# IQModulatorWaveyRadar.net
KiCad netlist of a schematic drawn in Altium Designer
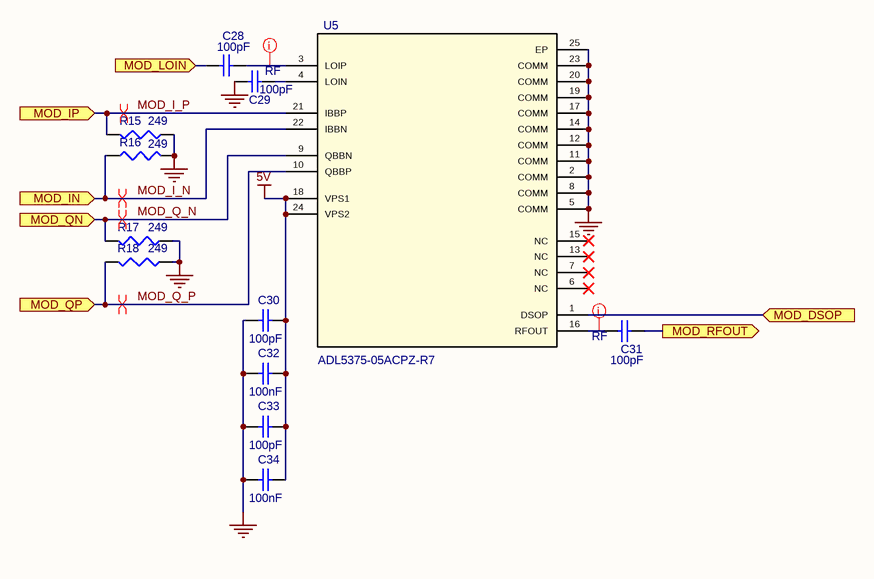
[diagram p0: IQModulatorWaveyRadar.SchDoc]

(export (version "E")
  (design (tool "Eeschema 10.0.6"))
  (components
    (comp (ref "C28")
      (value "100pF")
      (footprint "CAPC1005X56X25LL10T15")
      (fields (field (name "Comment") "04023A101JAT2A"))
      (libsource (lib "University of South Florida") (part "CAP-NP-2"))
    )
    (comp (ref "C29")
      (value "100pF")
      (footprint "CAPC1005X56X25LL10T15")
      (fields (field (name "Comment") "04023A101JAT2A"))
      (libsource (lib "University of South Florida") (part "CAP-NP-2"))
    )
    (comp (ref "C30")
      (value "100pF")
      (footprint "CAPC1005X56X25LL10T15")
      (fields (field (name "Comment") "04023A101JAT2A"))
      (libsource (lib "University of South Florida") (part "CAP-NP-2"))
    )
    (comp (ref "C31")
      (value "100pF")
      (footprint "CAPC1005X56X25LL10T15")
      (fields (field (name "Comment") "04023A101JAT2A"))
      (libsource (lib "University of South Florida") (part "CAP-NP-2"))
    )
    (comp (ref "C32")
      (value "100nF")
      (footprint "CAPC0402(1005)60_L")
      (description "Chip Capacitor, 100nF +/-20%, 10V, 0402, Thickness 0.6 mm")
      (fields (field (name "TOLERANCE") "20%") (field (name "Comment") "Capacitor 100nF +/-20% 10V 0402"))
      (libsource (lib "University of South Florida") (part "CAP-NP-2"))
    )
    (comp (ref "C33")
      (value "100pF")
      (footprint "CAPC1005X56X25LL10T15")
      (fields (field (name "Comment") "04023A101JAT2A"))
      (libsource (lib "University of South Florida") (part "CAP-NP-2"))
    )
    (comp (ref "C34")
      (value "100nF")
      (footprint "CAPC0402(1005)60_L")
      (description "Chip Capacitor, 100nF +/-20%, 10V, 0402, Thickness 0.6 mm")
      (fields (field (name "TOLERANCE") "20%") (field (name "Comment") "Capacitor 100nF +/-20% 10V 0402"))
      (libsource (lib "University of South Florida") (part "CAP-NP-2"))
    )
    (comp (ref "R15")
      (value "249")
      (footprint "RESC1005X40X25NL05T05")
      (description "RESISTOR, 0402, 249R 1%, 0.1W")
      (fields (field (name "Comment") "ERJ-2RKF2490X"))
      (libsource (lib "University of South Florida") (part "ResistorSymbol"))
    )
    (comp (ref "R16")
      (value "249")
      (footprint "RESC1005X40X25NL05T05")
      (description "RESISTOR, 0402, 249R 1%, 0.1W")
      (fields (field (name "Comment") "ERJ-2RKF2490X"))
      (libsource (lib "University of South Florida") (part "ResistorSymbol"))
    )
    (comp (ref "R17")
      (value "249")
      (footprint "RESC1005X40X25NL05T05")
      (description "RESISTOR, 0402, 249R 1%, 0.1W")
      (fields (field (name "Comment") "ERJ-2RKF2490X"))
      (libsource (lib "University of South Florida") (part "ResistorSymbol"))
    )
    (comp (ref "R18")
      (value "249")
      (footprint "RESC1005X40X25NL05T05")
      (description "RESISTOR, 0402, 249R 1%, 0.1W")
      (fields (field (name "Comment") "ERJ-2RKF2490X"))
      (libsource (lib "University of South Florida") (part "ResistorSymbol"))
    )
    (comp (ref "U5")
      (value "ADL5375-05ACPZ-R7")
      (footprint "CP_24_7_ADI")
      (description "IC MOD QUAD 400MHZ-6GHZ 24LFCSP")
      (fields (field (name "COPYRIGHT") "Copyright (C) 2018 Accelerated Designs. All rights reserved"))
      (libsource (lib "University of South Florida") (part "ADL5375-05ACPZ-R7"))
    )
  )
  (nets
    (net (code "1") (name "/MOD_DSOP") (class "Default")
      (node (ref "U5") (pin "1") (pinfunction "DSOP_1") (pintype "passive"))
    )
    (net (code "2") (name "/MOD_I_N") (class "Default")
      (node (ref "R16") (pin "1") (pinfunction "1_1") (pintype "passive"))
      (node (ref "U5") (pin "22") (pinfunction "IBBN_22") (pintype "passive"))
    )
    (net (code "3") (name "/MOD_I_P") (class "Default")
      (node (ref "R15") (pin "2") (pinfunction "2_2") (pintype "passive"))
      (node (ref "U5") (pin "21") (pinfunction "IBBP_21") (pintype "passive"))
    )
    (net (code "4") (name "/MOD_LOIN") (class "Default")
      (node (ref "C28") (pin "1") (pinfunction "1_1") (pintype "passive"))
    )
    (net (code "5") (name "/MOD_Q_N") (class "Default")
      (node (ref "R17") (pin "2") (pinfunction "2_2") (pintype "passive"))
      (node (ref "U5") (pin "9") (pinfunction "QBBN_9") (pintype "passive"))
    )
    (net (code "6") (name "/MOD_Q_P") (class "Default")
      (node (ref "R18") (pin "2") (pinfunction "2_2") (pintype "passive"))
      (node (ref "U5") (pin "10") (pinfunction "QBBP_10") (pintype "passive"))
    )
    (net (code "7") (name "/MOD_RFOUT") (class "Default")
      (node (ref "C31") (pin "2") (pinfunction "2_2") (pintype "passive"))
    )
    (net (code "8") (name "5V") (class "Default")
      (node (ref "C30") (pin "2") (pinfunction "2_2") (pintype "passive"))
      (node (ref "C32") (pin "2") (pinfunction "2_2") (pintype "passive"))
      (node (ref "C33") (pin "2") (pinfunction "2_2") (pintype "passive"))
      (node (ref "C34") (pin "2") (pinfunction "2_2") (pintype "passive"))
      (node (ref "U5") (pin "18") (pinfunction "VPS1_18") (pintype "power_in"))
      (node (ref "U5") (pin "24") (pinfunction "VPS2_24") (pintype "power_in"))
    )
    (net (code "9") (name "GND") (class "Default")
      (node (ref "C29") (pin "1") (pinfunction "1_1") (pintype "passive"))
      (node (ref "C30") (pin "1") (pinfunction "1_1") (pintype "passive"))
      (node (ref "C32") (pin "1") (pinfunction "1_1") (pintype "passive"))
      (node (ref "C33") (pin "1") (pinfunction "1_1") (pintype "passive"))
      (node (ref "C34") (pin "1") (pinfunction "1_1") (pintype "passive"))
      (node (ref "R15") (pin "1") (pinfunction "1_1") (pintype "passive"))
      (node (ref "R16") (pin "2") (pinfunction "2_2") (pintype "passive"))
      (node (ref "R17") (pin "1") (pinfunction "1_1") (pintype "passive"))
      (node (ref "R18") (pin "1") (pinfunction "1_1") (pintype "passive"))
      (node (ref "U5") (pin "11") (pinfunction "COMM_11") (pintype "passive"))
      (node (ref "U5") (pin "12") (pinfunction "COMM_12") (pintype "passive"))
      (node (ref "U5") (pin "14") (pinfunction "COMM_14") (pintype "passive"))
      (node (ref "U5") (pin "17") (pinfunction "COMM_17") (pintype "passive"))
      (node (ref "U5") (pin "19") (pinfunction "COMM_19") (pintype "passive"))
      (node (ref "U5") (pin "2") (pinfunction "COMM_2") (pintype "passive"))
      (node (ref "U5") (pin "20") (pinfunction "COMM_20") (pintype "passive"))
      (node (ref "U5") (pin "23") (pinfunction "COMM_23") (pintype "passive"))
      (node (ref "U5") (pin "25") (pinfunction "EP_25") (pintype "passive"))
      (node (ref "U5") (pin "5") (pinfunction "COMM_5") (pintype "passive"))
      (node (ref "U5") (pin "8") (pinfunction "COMM_8") (pintype "passive"))
    )
    (net (code "10") (name "Net-(U5-LOIN)") (class "Default")
      (node (ref "C29") (pin "2") (pinfunction "2_2") (pintype "passive"))
      (node (ref "U5") (pin "4") (pinfunction "LOIN_4") (pintype "passive"))
    )
    (net (code "11") (name "Net-(U5-LOIP)") (class "Default")
      (node (ref "C28") (pin "2") (pinfunction "2_2") (pintype "passive"))
      (node (ref "U5") (pin "3") (pinfunction "LOIP_3") (pintype "passive"))
    )
    (net (code "12") (name "Net-(U5-RFOUT)") (class "Default")
      (node (ref "C31") (pin "1") (pinfunction "1_1") (pintype "passive"))
      (node (ref "U5") (pin "16") (pinfunction "RFOUT_16") (pintype "passive"))
    )
    (net (code "13") (name "unconnected-(U5-NC-Pad6)") (class "Default")
      (node (ref "U5") (pin "6") (pinfunction "NC_6") (pintype "passive+no_connect"))
    )
    (net (code "14") (name "unconnected-(U5-NC-Pad7)") (class "Default")
      (node (ref "U5") (pin "7") (pinfunction "NC_7") (pintype "passive+no_connect"))
    )
    (net (code "15") (name "unconnected-(U5-NC-Pad13)") (class "Default")
      (node (ref "U5") (pin "13") (pinfunction "NC_13") (pintype "passive+no_connect"))
    )
    (net (code "16") (name "unconnected-(U5-NC-Pad15)") (class "Default")
      (node (ref "U5") (pin "15") (pinfunction "NC_15") (pintype "passive+no_connect"))
    )
  )
)
